# RS232_RS485_INTERFACE.net
KiCad netlist of a schematic drawn in Altium Designer
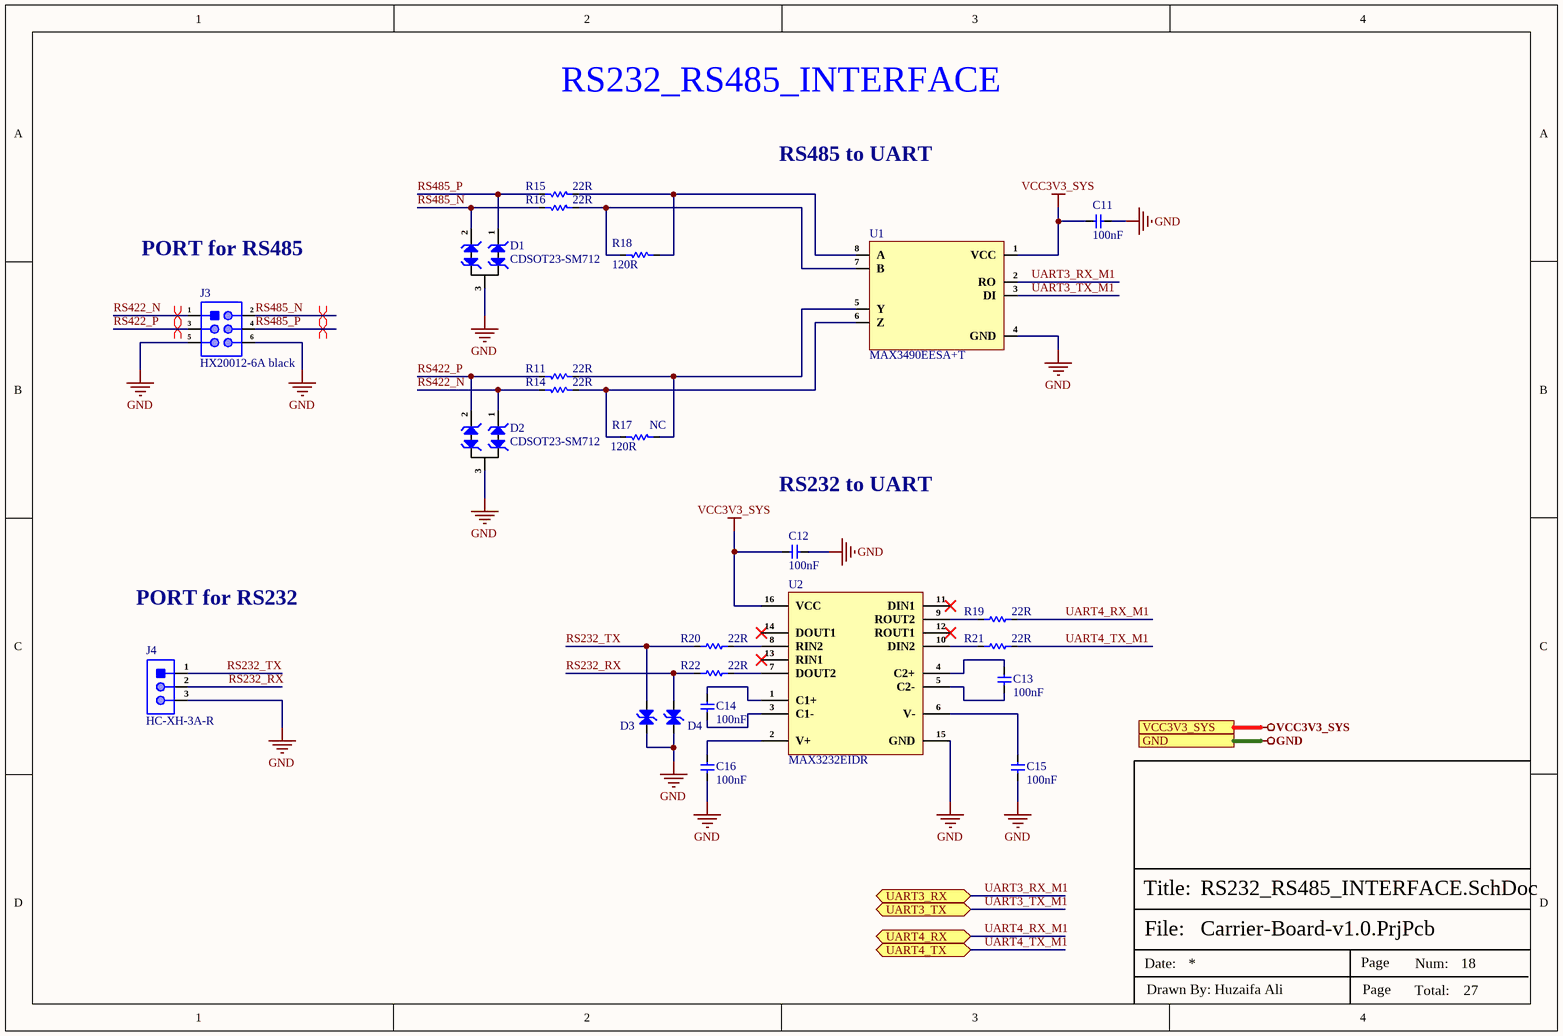
[diagram p0: RS232_RS485_INTERFACE.SchDoc]

(export (version "E")
  (design (tool "Eeschema 10.0.6"))
  (components
    (comp (ref "C11")
      (value "100nF")
      (footprint "Cap-0402")
      (description "CAP CER 0.1UF 16V X5R 0402")
      (fields
        (field (name "MANUFACTURER") "Yageo")
        (field (name "MANUFACTURER PART NUMBER") "CC0402KRX5R7BB104")
      )
      (libsource (lib "eSpark Libraries") (part "CC0402KRX5R7BB104"))
    )
    (comp (ref "C12")
      (value "100nF")
      (footprint "Cap-0402")
      (description "CAP CER 0.1UF 16V X5R 0402")
      (fields
        (field (name "MANUFACTURER") "Yageo")
        (field (name "MANUFACTURER PART NUMBER") "CC0402KRX5R7BB104")
      )
      (libsource (lib "eSpark Libraries") (part "CC0402KRX5R7BB104"))
    )
    (comp (ref "C13")
      (value "100nF")
      (footprint "Cap-0402")
      (description "CAP CER 0.1UF 16V X5R 0402")
      (fields
        (field (name "MANUFACTURER") "Yageo")
        (field (name "MANUFACTURER PART NUMBER") "CC0402KRX5R7BB104")
      )
      (libsource (lib "eSpark Libraries") (part "CC0402KRX5R7BB104"))
    )
    (comp (ref "C14")
      (value "100nF")
      (footprint "Cap-0402")
      (description "CAP CER 0.1UF 16V X5R 0402")
      (fields
        (field (name "MANUFACTURER") "Yageo")
        (field (name "MANUFACTURER PART NUMBER") "CC0402KRX5R7BB104")
      )
      (libsource (lib "eSpark Libraries") (part "CC0402KRX5R7BB104"))
    )
    (comp (ref "C15")
      (value "100nF")
      (footprint "Cap-0402")
      (description "CAP CER 0.1UF 16V X5R 0402")
      (fields
        (field (name "MANUFACTURER") "Yageo")
        (field (name "MANUFACTURER PART NUMBER") "CC0402KRX5R7BB104")
      )
      (libsource (lib "eSpark Libraries") (part "CC0402KRX5R7BB104"))
    )
    (comp (ref "C16")
      (value "100nF")
      (footprint "Cap-0402")
      (description "CAP CER 0.1UF 16V X5R 0402")
      (fields
        (field (name "MANUFACTURER") "Yageo")
        (field (name "MANUFACTURER PART NUMBER") "CC0402KRX5R7BB104")
      )
      (libsource (lib "eSpark Libraries") (part "CC0402KRX5R7BB104"))
    )
    (comp (ref "D1")
      (value "CDSOT23-SM712")
      (footprint "SOT-23")
      (description "TVS DIODE 7V/12V 14V/26V SOT23-3")
      (fields (field (name "MANUFACTURER") "Bourns") (field (name "LCSC PART NUMBER") "C404012"))
      (libsource (lib "eSpark Libraries") (part "CDSOT23-SM712"))
    )
    (comp (ref "D2")
      (value "CDSOT23-SM712")
      (footprint "SOT-23")
      (description "TVS DIODE 7V/12V 14V/26V SOT23-3")
      (fields (field (name "MANUFACTURER") "Bourns") (field (name "LCSC PART NUMBER") "C404012"))
      (libsource (lib "eSpark Libraries") (part "CDSOT23-SM712"))
    )
    (comp (ref "D3")
      (value "ESD5451N")
      (footprint "DFN1006-2L (Bi-Directional)")
      (description "DFN1006-2(0402) ESD Protection Devices ROHS")
      (fields (field (name "MANUFACTURER") "TECH PUBLIC") (field (name "LCSC PART NUMBER") "C2936977"))
      (libsource (lib "eSpark Libraries") (part "ESD5451N"))
    )
    (comp (ref "D4")
      (value "ESD5451N")
      (footprint "DFN1006-2L (Bi-Directional)")
      (description "DFN1006-2(0402) ESD Protection Devices ROHS")
      (fields (field (name "MANUFACTURER") "TECH PUBLIC") (field (name "LCSC PART NUMBER") "C2936977"))
      (libsource (lib "eSpark Libraries") (part "ESD5451N"))
    )
    (comp (ref "J3")
      (value "HX20012-6A black")
      (footprint "HX20012-6A black")
      (fields
        (field (name "MANUFACTURER") "HX(Zhejiang Yueqing Hongxing Elec)")
        (field (name "LCSC PART NUMBER") "C469723")
      )
      (libsource (lib "eSpark Libraries") (part "HX20012-6A black"))
    )
    (comp (ref "J4")
      (value "HC-XH-3A-R")
      (footprint "HC-XH-3A-R")
      (description "1x3P 3P XH 1 Tin 2.5mm 3 -25℃~+85℃ Brass 3A Straight Plugin,P=2.5mm Wire To Board Connector ROHS")
      (fields (field (name "MANUFACTURER") "HCTL") (field (name "LCSC PART NUMBER") "C7466690"))
      (libsource (lib "eSpark Libraries") (part "HC-XH-3A-R"))
    )
    (comp (ref "R11")
      (value "22R")
      (footprint "Res-0402")
      (description "RES 22 OHM 1% 1/16W 0402")
      (fields
        (field (name "MANUFACTURER") "Yageo")
        (field (name "MANUFACTURER PART NUMBER") "RC0402FR-0722RL")
      )
      (libsource (lib "eSpark Libraries") (part "RC0402FR-0722RL"))
    )
    (comp (ref "R14")
      (value "22R")
      (footprint "Res-0402")
      (description "RES 22 OHM 1% 1/16W 0402")
      (fields
        (field (name "MANUFACTURER") "Yageo")
        (field (name "MANUFACTURER PART NUMBER") "RC0402FR-0722RL")
      )
      (libsource (lib "eSpark Libraries") (part "RC0402FR-0722RL"))
    )
    (comp (ref "R15")
      (value "22R")
      (footprint "Res-0402")
      (description "RES 22 OHM 1% 1/16W 0402")
      (fields
        (field (name "MANUFACTURER") "Yageo")
        (field (name "MANUFACTURER PART NUMBER") "RC0402FR-0722RL")
      )
      (libsource (lib "eSpark Libraries") (part "RC0402FR-0722RL"))
    )
    (comp (ref "R16")
      (value "22R")
      (footprint "Res-0402")
      (description "RES 22 OHM 1% 1/16W 0402")
      (fields
        (field (name "MANUFACTURER") "Yageo")
        (field (name "MANUFACTURER PART NUMBER") "RC0402FR-0722RL")
      )
      (libsource (lib "eSpark Libraries") (part "RC0402FR-0722RL"))
    )
    (comp (ref "R17")
      (value "NC")
      (footprint "Res-0603")
      (description "RES SMD 120 OHM 0.1% 1/10W 0603")
      (fields
        (field (name "MANUFACTURER") "Yageo")
        (field (name "MANUFACTURER PART NUMBER") "RT0603BRB07120RL")
      )
      (libsource (lib "eSpark Libraries") (part "RT0603BRB07120RL"))
    )
    (comp (ref "R18")
      (value "120R")
      (footprint "Res-0603")
      (description "RES SMD 120 OHM 0.1% 1/10W 0603")
      (fields
        (field (name "MANUFACTURER") "Yageo")
        (field (name "MANUFACTURER PART NUMBER") "RT0603BRB07120RL")
      )
      (libsource (lib "eSpark Libraries") (part "RT0603BRB07120RL"))
    )
    (comp (ref "R19")
      (value "22R")
      (footprint "Res-0402")
      (description "RES 22 OHM 1% 1/16W 0402")
      (fields
        (field (name "MANUFACTURER") "Yageo")
        (field (name "MANUFACTURER PART NUMBER") "RC0402FR-0722RL")
      )
      (libsource (lib "eSpark Libraries") (part "RC0402FR-0722RL"))
    )
    (comp (ref "R20")
      (value "22R")
      (footprint "Res-0402")
      (description "RES 22 OHM 1% 1/16W 0402")
      (fields
        (field (name "MANUFACTURER") "Yageo")
        (field (name "MANUFACTURER PART NUMBER") "RC0402FR-0722RL")
      )
      (libsource (lib "eSpark Libraries") (part "RC0402FR-0722RL"))
    )
    (comp (ref "R21")
      (value "22R")
      (footprint "Res-0402")
      (description "RES 22 OHM 1% 1/16W 0402")
      (fields
        (field (name "MANUFACTURER") "Yageo")
        (field (name "MANUFACTURER PART NUMBER") "RC0402FR-0722RL")
      )
      (libsource (lib "eSpark Libraries") (part "RC0402FR-0722RL"))
    )
    (comp (ref "R22")
      (value "22R")
      (footprint "Res-0402")
      (description "RES 22 OHM 1% 1/16W 0402")
      (fields
        (field (name "MANUFACTURER") "Yageo")
        (field (name "MANUFACTURER PART NUMBER") "RC0402FR-0722RL")
      )
      (libsource (lib "eSpark Libraries") (part "RC0402FR-0722RL"))
    )
    (comp (ref "U1")
      (value "MAX3490EESA+T")
      (footprint "SOIC-8(0.154\", 3.90mm Width)")
      (description "IC TXRX RS485/422 10MBPS 8SOIC")
      (fields (field (name "MANUFACTURER") "Maxim") (field (name "LCSC PART NUMBER") "C5342105"))
      (libsource (lib "eSpark Libraries") (part "MAX3490EESA+T"))
    )
    (comp (ref "U2")
      (value "MAX3232EIDR")
      (footprint "SOIC-16")
      (description "IC RS232 LINE DVR/RCVR 16-SOIC")
      (fields (field (name "MANUFACTURER") "Texas Instruments"))
      (libsource (lib "eSpark Libraries") (part "MAX3232EIDR"))
    )
  )
  (nets
    (net (code "1") (name "/RS232_RX") (class "Default")
      (node (ref "D4") (pin "2") (pinfunction "K_2") (pintype "passive"))
      (node (ref "J4") (pin "2") (pinfunction "2_2") (pintype "passive"))
      (node (ref "R22") (pin "1") (pinfunction "1_1") (pintype "passive"))
    )
    (net (code "2") (name "/RS232_TX") (class "Default")
      (node (ref "D3") (pin "2") (pinfunction "K_2") (pintype "passive"))
      (node (ref "J4") (pin "1") (pinfunction "1_1") (pintype "passive"))
      (node (ref "R20") (pin "1") (pinfunction "1_1") (pintype "passive"))
    )
    (net (code "3") (name "/RS422_N") (class "Default")
      (node (ref "D2") (pin "1") (pinfunction "IO1_1") (pintype "passive"))
      (node (ref "J3") (pin "1") (pinfunction "1_1") (pintype "passive"))
      (node (ref "R14") (pin "2") (pinfunction "2_2") (pintype "passive"))
    )
    (net (code "4") (name "/RS422_P") (class "Default")
      (node (ref "D2") (pin "2") (pinfunction "IO2_2") (pintype "passive"))
      (node (ref "J3") (pin "3") (pinfunction "3_3") (pintype "passive"))
      (node (ref "R11") (pin "2") (pinfunction "2_2") (pintype "passive"))
    )
    (net (code "5") (name "/RS485_N") (class "Default")
      (node (ref "D1") (pin "2") (pinfunction "IO2_2") (pintype "passive"))
      (node (ref "J3") (pin "2") (pinfunction "2_2") (pintype "passive"))
      (node (ref "R16") (pin "2") (pinfunction "2_2") (pintype "passive"))
    )
    (net (code "6") (name "/RS485_P") (class "Default")
      (node (ref "D1") (pin "1") (pinfunction "IO1_1") (pintype "passive"))
      (node (ref "J3") (pin "4") (pinfunction "4_4") (pintype "passive"))
      (node (ref "R15") (pin "2") (pinfunction "2_2") (pintype "passive"))
    )
    (net (code "7") (name "/UART3_RX_M1") (class "Default")
      (node (ref "U1") (pin "2") (pinfunction "RO_2") (pintype "passive"))
    )
    (net (code "8") (name "/UART3_TX_M1") (class "Default")
      (node (ref "U1") (pin "3") (pinfunction "DI_3") (pintype "passive"))
    )
    (net (code "9") (name "/UART4_RX_M1") (class "Default")
      (node (ref "R19") (pin "2") (pinfunction "2_2") (pintype "passive"))
    )
    (net (code "10") (name "/UART4_TX_M1") (class "Default")
      (node (ref "R21") (pin "2") (pinfunction "2_2") (pintype "passive"))
    )
    (net (code "11") (name "GND") (class "Default")
      (node (ref "C11") (pin "2") (pinfunction "2_2") (pintype "passive"))
      (node (ref "C12") (pin "2") (pinfunction "2_2") (pintype "passive"))
      (node (ref "C15") (pin "2") (pinfunction "2_2") (pintype "passive"))
      (node (ref "C16") (pin "2") (pinfunction "2_2") (pintype "passive"))
      (node (ref "D1") (pin "3") (pinfunction "GND_3") (pintype "passive"))
      (node (ref "D2") (pin "3") (pinfunction "GND_3") (pintype "passive"))
      (node (ref "D3") (pin "1") (pinfunction "K_1") (pintype "passive"))
      (node (ref "D4") (pin "1") (pinfunction "K_1") (pintype "passive"))
      (node (ref "J3") (pin "5") (pinfunction "5_5") (pintype "passive"))
      (node (ref "J3") (pin "6") (pinfunction "6_6") (pintype "passive"))
      (node (ref "J4") (pin "3") (pinfunction "3_3") (pintype "passive"))
      (node (ref "U1") (pin "4") (pinfunction "GND_4") (pintype "passive"))
      (node (ref "U2") (pin "15") (pinfunction "GND_15") (pintype "passive"))
    )
    (net (code "12") (name "Net-(U1-A)") (class "Default")
      (node (ref "R15") (pin "1") (pinfunction "1_1") (pintype "passive"))
      (node (ref "R18") (pin "1") (pinfunction "1_1") (pintype "passive"))
      (node (ref "U1") (pin "8") (pinfunction "A_8") (pintype "passive"))
    )
    (net (code "13") (name "Net-(U1-B)") (class "Default")
      (node (ref "R16") (pin "1") (pinfunction "1_1") (pintype "passive"))
      (node (ref "R18") (pin "2") (pinfunction "2_2") (pintype "passive"))
      (node (ref "U1") (pin "7") (pinfunction "B_7") (pintype "passive"))
    )
    (net (code "14") (name "Net-(U1-Y)") (class "Default")
      (node (ref "R11") (pin "1") (pinfunction "1_1") (pintype "passive"))
      (node (ref "R17") (pin "1") (pinfunction "1_1") (pintype "passive"))
      (node (ref "U1") (pin "5") (pinfunction "Y_5") (pintype "passive"))
    )
    (net (code "15") (name "Net-(U1-Z)") (class "Default")
      (node (ref "R14") (pin "1") (pinfunction "1_1") (pintype "passive"))
      (node (ref "R17") (pin "2") (pinfunction "2_2") (pintype "passive"))
      (node (ref "U1") (pin "6") (pinfunction "Z_6") (pintype "passive"))
    )
    (net (code "16") (name "Net-(U2-C1+)") (class "Default")
      (node (ref "C14") (pin "1") (pinfunction "1_1") (pintype "passive"))
      (node (ref "U2") (pin "1") (pinfunction "C1+_1") (pintype "passive"))
    )
    (net (code "17") (name "Net-(U2-C1-)") (class "Default")
      (node (ref "C14") (pin "2") (pinfunction "2_2") (pintype "passive"))
      (node (ref "U2") (pin "3") (pinfunction "C1-_3") (pintype "passive"))
    )
    (net (code "18") (name "Net-(U2-C2+)") (class "Default")
      (node (ref "C13") (pin "1") (pinfunction "1_1") (pintype "passive"))
      (node (ref "U2") (pin "4") (pinfunction "C2+_4") (pintype "passive"))
    )
    (net (code "19") (name "Net-(U2-C2-)") (class "Default")
      (node (ref "C13") (pin "2") (pinfunction "2_2") (pintype "passive"))
      (node (ref "U2") (pin "5") (pinfunction "C2-_5") (pintype "passive"))
    )
    (net (code "20") (name "Net-(U2-DIN2)") (class "Default")
      (node (ref "R21") (pin "1") (pinfunction "1_1") (pintype "passive"))
      (node (ref "U2") (pin "10") (pinfunction "DIN2_10") (pintype "passive"))
    )
    (net (code "21") (name "Net-(U2-DOUT2)") (class "Default")
      (node (ref "R22") (pin "2") (pinfunction "2_2") (pintype "passive"))
      (node (ref "U2") (pin "7") (pinfunction "DOUT2_7") (pintype "passive"))
    )
    (net (code "22") (name "Net-(U2-RIN2)") (class "Default")
      (node (ref "R20") (pin "2") (pinfunction "2_2") (pintype "passive"))
      (node (ref "U2") (pin "8") (pinfunction "RIN2_8") (pintype "passive"))
    )
    (net (code "23") (name "Net-(U2-ROUT2)") (class "Default")
      (node (ref "R19") (pin "1") (pinfunction "1_1") (pintype "passive"))
      (node (ref "U2") (pin "9") (pinfunction "ROUT2_9") (pintype "passive"))
    )
    (net (code "24") (name "Net-(U2-V+)") (class "Default")
      (node (ref "C16") (pin "1") (pinfunction "1_1") (pintype "passive"))
      (node (ref "U2") (pin "2") (pinfunction "V+_2") (pintype "passive"))
    )
    (net (code "25") (name "Net-(U2-V-)") (class "Default")
      (node (ref "C15") (pin "1") (pinfunction "1_1") (pintype "passive"))
      (node (ref "U2") (pin "6") (pinfunction "V-_6") (pintype "passive"))
    )
    (net (code "26") (name "VCC3V3_SYS") (class "Default")
      (node (ref "C11") (pin "1") (pinfunction "1_1") (pintype "passive"))
      (node (ref "C12") (pin "1") (pinfunction "1_1") (pintype "passive"))
      (node (ref "U1") (pin "1") (pinfunction "VCC_1") (pintype "passive"))
      (node (ref "U2") (pin "16") (pinfunction "VCC_16") (pintype "passive"))
    )
    (net (code "27") (name "unconnected-(U2-DIN1-Pad11)") (class "Default")
      (node (ref "U2") (pin "11") (pinfunction "DIN1_11") (pintype "passive+no_connect"))
    )
    (net (code "28") (name "unconnected-(U2-DOUT1-Pad14)") (class "Default")
      (node (ref "U2") (pin "14") (pinfunction "DOUT1_14") (pintype "passive+no_connect"))
    )
    (net (code "29") (name "unconnected-(U2-RIN1-Pad13)") (class "Default")
      (node (ref "U2") (pin "13") (pinfunction "RIN1_13") (pintype "passive+no_connect"))
    )
    (net (code "30") (name "unconnected-(U2-ROUT1-Pad12)") (class "Default")
      (node (ref "U2") (pin "12") (pinfunction "ROUT1_12") (pintype "passive+no_connect"))
    )
  )
)
